# krokovy_motor_pokus.net
KiCad netlist of a schematic drawn in EAGLE
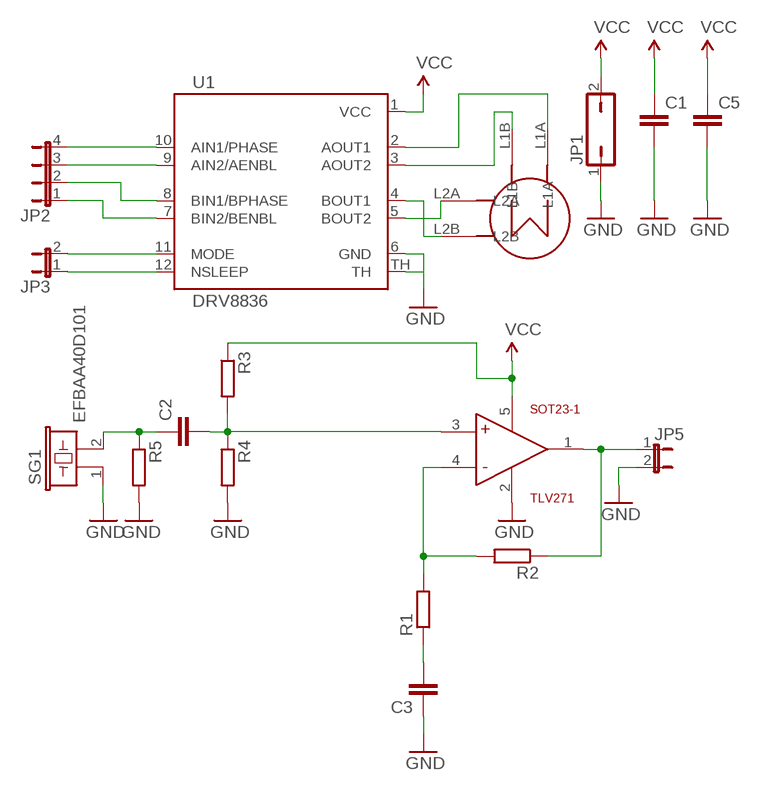
[diagram p0: schematic, sheet 1]

(export (version "E")
  (design (tool "Eeschema 10.0.6"))
  (components
    (comp (ref "C1")
      (value "CC1206")
      (footprint "eagle-import:C1206")
      (libsource (lib "eagle-import") (part "CC1206"))
    )
    (comp (ref "C2")
      (value "CC1206")
      (footprint "eagle-import:C1206")
      (libsource (lib "eagle-import") (part "CC1206"))
    )
    (comp (ref "C3")
      (value "CC1206")
      (footprint "eagle-import:C1206")
      (libsource (lib "eagle-import") (part "CC1206"))
    )
    (comp (ref "C5")
      (value "CC1206")
      (footprint "eagle-import:C1206")
      (libsource (lib "eagle-import") (part "CC1206"))
    )
    (comp (ref "JP1")
      (value "JP1Q")
      (footprint "eagle-import:JP1")
      (libsource (lib "eagle-import") (part "JP1Q"))
    )
    (comp (ref "JP2")
      (value "JP4E")
      (footprint "eagle-import:JP4")
      (libsource (lib "eagle-import") (part "JP4E"))
    )
    (comp (ref "JP3")
      (value "JP1E")
      (footprint "eagle-import:JP1")
      (libsource (lib "eagle-import") (part "JP1E"))
    )
    (comp (ref "JP5")
      (value "JP1E")
      (footprint "eagle-import:JP1")
      (libsource (lib "eagle-import") (part "JP1E"))
    )
    (comp (ref "R1")
      (value "RR1206")
      (footprint "eagle-import:R1206")
      (libsource (lib "eagle-import") (part "RR1206"))
    )
    (comp (ref "R2")
      (value "RR1206")
      (footprint "eagle-import:R1206")
      (libsource (lib "eagle-import") (part "RR1206"))
    )
    (comp (ref "R3")
      (value "RR1206")
      (footprint "eagle-import:R1206")
      (libsource (lib "eagle-import") (part "RR1206"))
    )
    (comp (ref "R4")
      (value "RR1206")
      (footprint "eagle-import:R1206")
      (libsource (lib "eagle-import") (part "RR1206"))
    )
    (comp (ref "R5")
      (value "RR1206")
      (footprint "eagle-import:R1206")
      (libsource (lib "eagle-import") (part "RR1206"))
    )
    (comp (ref "SG1")
      (value "EFBAA40D101")
      (footprint "eagle-import:EFBAA40D101")
      (libsource (lib "eagle-import") (part "EFB?AA40D101"))
    )
    (comp (ref "SOT23-1")
      (value "TLV271")
      (footprint "eagle-import:SOT23-5")
      (libsource (lib "eagle-import") (part "TLV271"))
    )
    (comp (ref "U$1")
      (value "STEP_MOTOR")
      (footprint "eagle-import:STEP_MOTOR")
      (libsource (lib "eagle-import") (part "STEP_MOTOR"))
    )
    (comp (ref "U1")
      (value "DRV8836")
      (footprint "eagle-import:12WSON")
      (libsource (lib "eagle-import") (part "DRV8836"))
    )
  )
  (nets
    (net (code "1") (name "GND") (class "Default")
      (node (ref "C1") (pin "2") (pinfunction "2_2") (pintype "passive"))
      (node (ref "C3") (pin "1") (pinfunction "1_1") (pintype "passive"))
      (node (ref "C5") (pin "2") (pinfunction "2_2") (pintype "passive"))
      (node (ref "JP1") (pin "1") (pinfunction "1_1") (pintype "passive"))
      (node (ref "JP5") (pin "2") (pinfunction "2_2") (pintype "passive"))
      (node (ref "R4") (pin "2") (pinfunction "2_2") (pintype "passive"))
      (node (ref "R5") (pin "2") (pinfunction "2_2") (pintype "passive"))
      (node (ref "SG1") (pin "1") (pinfunction "1_1") (pintype "passive"))
      (node (ref "SOT23-1") (pin "2") (pinfunction "GND_2") (pintype "power_in"))
      (node (ref "U1") (pin "6") (pinfunction "GND_6") (pintype "bidirectional"))
      (node (ref "U1") (pin "TH") (pinfunction "TH_TH") (pintype "bidirectional"))
    )
    (net (code "2") (name "Net-(C2-Pad1)") (class "Default")
      (node (ref "C2") (pin "1") (pinfunction "1_1") (pintype "passive"))
      (node (ref "R5") (pin "1") (pinfunction "1_1") (pintype "passive"))
      (node (ref "SG1") (pin "2") (pinfunction "2_2") (pintype "passive"))
    )
    (net (code "3") (name "Net-(C3-Pad2)") (class "Default")
      (node (ref "C3") (pin "2") (pinfunction "2_2") (pintype "passive"))
      (node (ref "R1") (pin "1") (pinfunction "1_1") (pintype "passive"))
    )
    (net (code "4") (name "Net-(SOT23-1-IN+)") (class "Default")
      (node (ref "C2") (pin "2") (pinfunction "2_2") (pintype "passive"))
      (node (ref "R3") (pin "2") (pinfunction "2_2") (pintype "passive"))
      (node (ref "R4") (pin "1") (pinfunction "1_1") (pintype "passive"))
      (node (ref "SOT23-1") (pin "3") (pinfunction "IN+_3") (pintype "input"))
    )
    (net (code "5") (name "Net-(SOT23-1-IN-)") (class "Default")
      (node (ref "R1") (pin "2") (pinfunction "2_2") (pintype "passive"))
      (node (ref "R2") (pin "2") (pinfunction "2_2") (pintype "passive"))
      (node (ref "SOT23-1") (pin "4") (pinfunction "IN-_4") (pintype "input"))
    )
    (net (code "6") (name "Net-(SOT23-1-OUT)") (class "Default")
      (node (ref "JP5") (pin "1") (pinfunction "1_1") (pintype "passive"))
      (node (ref "R2") (pin "1") (pinfunction "1_1") (pintype "passive"))
      (node (ref "SOT23-1") (pin "1") (pinfunction "OUT_1") (pintype "output"))
    )
    (net (code "7") (name "Net-(U1-AIN1{slash}PHASE)") (class "Default")
      (node (ref "JP2") (pin "4") (pinfunction "4_4") (pintype "passive"))
      (node (ref "U1") (pin "10") (pinfunction "AIN1/PHASE_10") (pintype "bidirectional"))
    )
    (net (code "8") (name "Net-(U1-AIN2{slash}AENBL)") (class "Default")
      (node (ref "JP2") (pin "3") (pinfunction "3_3") (pintype "passive"))
      (node (ref "U1") (pin "9") (pinfunction "AIN2/AENBL_9") (pintype "bidirectional"))
    )
    (net (code "9") (name "Net-(U1-AOUT1)") (class "Default")
      (node (ref "U$1") (pin "L1A") (pinfunction "L1A_L1A") (pintype "bidirectional"))
      (node (ref "U1") (pin "2") (pinfunction "AOUT1_2") (pintype "bidirectional"))
    )
    (net (code "10") (name "Net-(U1-AOUT2)") (class "Default")
      (node (ref "U$1") (pin "L1B") (pinfunction "L1B_L1B") (pintype "bidirectional"))
      (node (ref "U1") (pin "3") (pinfunction "AOUT2_3") (pintype "bidirectional"))
    )
    (net (code "11") (name "Net-(U1-BIN1{slash}BPHASE)") (class "Default")
      (node (ref "JP2") (pin "2") (pinfunction "2_2") (pintype "passive"))
      (node (ref "U1") (pin "8") (pinfunction "BIN1/BPHASE_8") (pintype "bidirectional"))
    )
    (net (code "12") (name "Net-(U1-BIN2{slash}BENBL)") (class "Default")
      (node (ref "JP2") (pin "1") (pinfunction "1_1") (pintype "passive"))
      (node (ref "U1") (pin "7") (pinfunction "BIN2/BENBL_7") (pintype "bidirectional"))
    )
    (net (code "13") (name "Net-(U1-BOUT1)") (class "Default")
      (node (ref "U$1") (pin "L2B") (pinfunction "L2B_L2B") (pintype "bidirectional"))
      (node (ref "U1") (pin "4") (pinfunction "BOUT1_4") (pintype "bidirectional"))
    )
    (net (code "14") (name "Net-(U1-BOUT2)") (class "Default")
      (node (ref "U$1") (pin "L2A") (pinfunction "L2A_L2A") (pintype "bidirectional"))
      (node (ref "U1") (pin "5") (pinfunction "BOUT2_5") (pintype "bidirectional"))
    )
    (net (code "15") (name "Net-(U1-MODE)") (class "Default")
      (node (ref "JP3") (pin "2") (pinfunction "2_2") (pintype "passive"))
      (node (ref "U1") (pin "11") (pinfunction "MODE_11") (pintype "bidirectional"))
    )
    (net (code "16") (name "Net-(U1-NSLEEP)") (class "Default")
      (node (ref "JP3") (pin "1") (pinfunction "1_1") (pintype "passive"))
      (node (ref "U1") (pin "12") (pinfunction "NSLEEP_12") (pintype "bidirectional"))
    )
    (net (code "17") (name "VCC") (class "Default")
      (node (ref "C1") (pin "1") (pinfunction "1_1") (pintype "passive"))
      (node (ref "C5") (pin "1") (pinfunction "1_1") (pintype "passive"))
      (node (ref "JP1") (pin "2") (pinfunction "2_2") (pintype "passive"))
      (node (ref "R3") (pin "1") (pinfunction "1_1") (pintype "passive"))
      (node (ref "SOT23-1") (pin "5") (pinfunction "VDD_5") (pintype "power_in"))
      (node (ref "U1") (pin "1") (pinfunction "VCC_1") (pintype "bidirectional"))
    )
  )
)
